# Neutron_v1.net
KiCad netlist of a schematic drawn in EAGLE
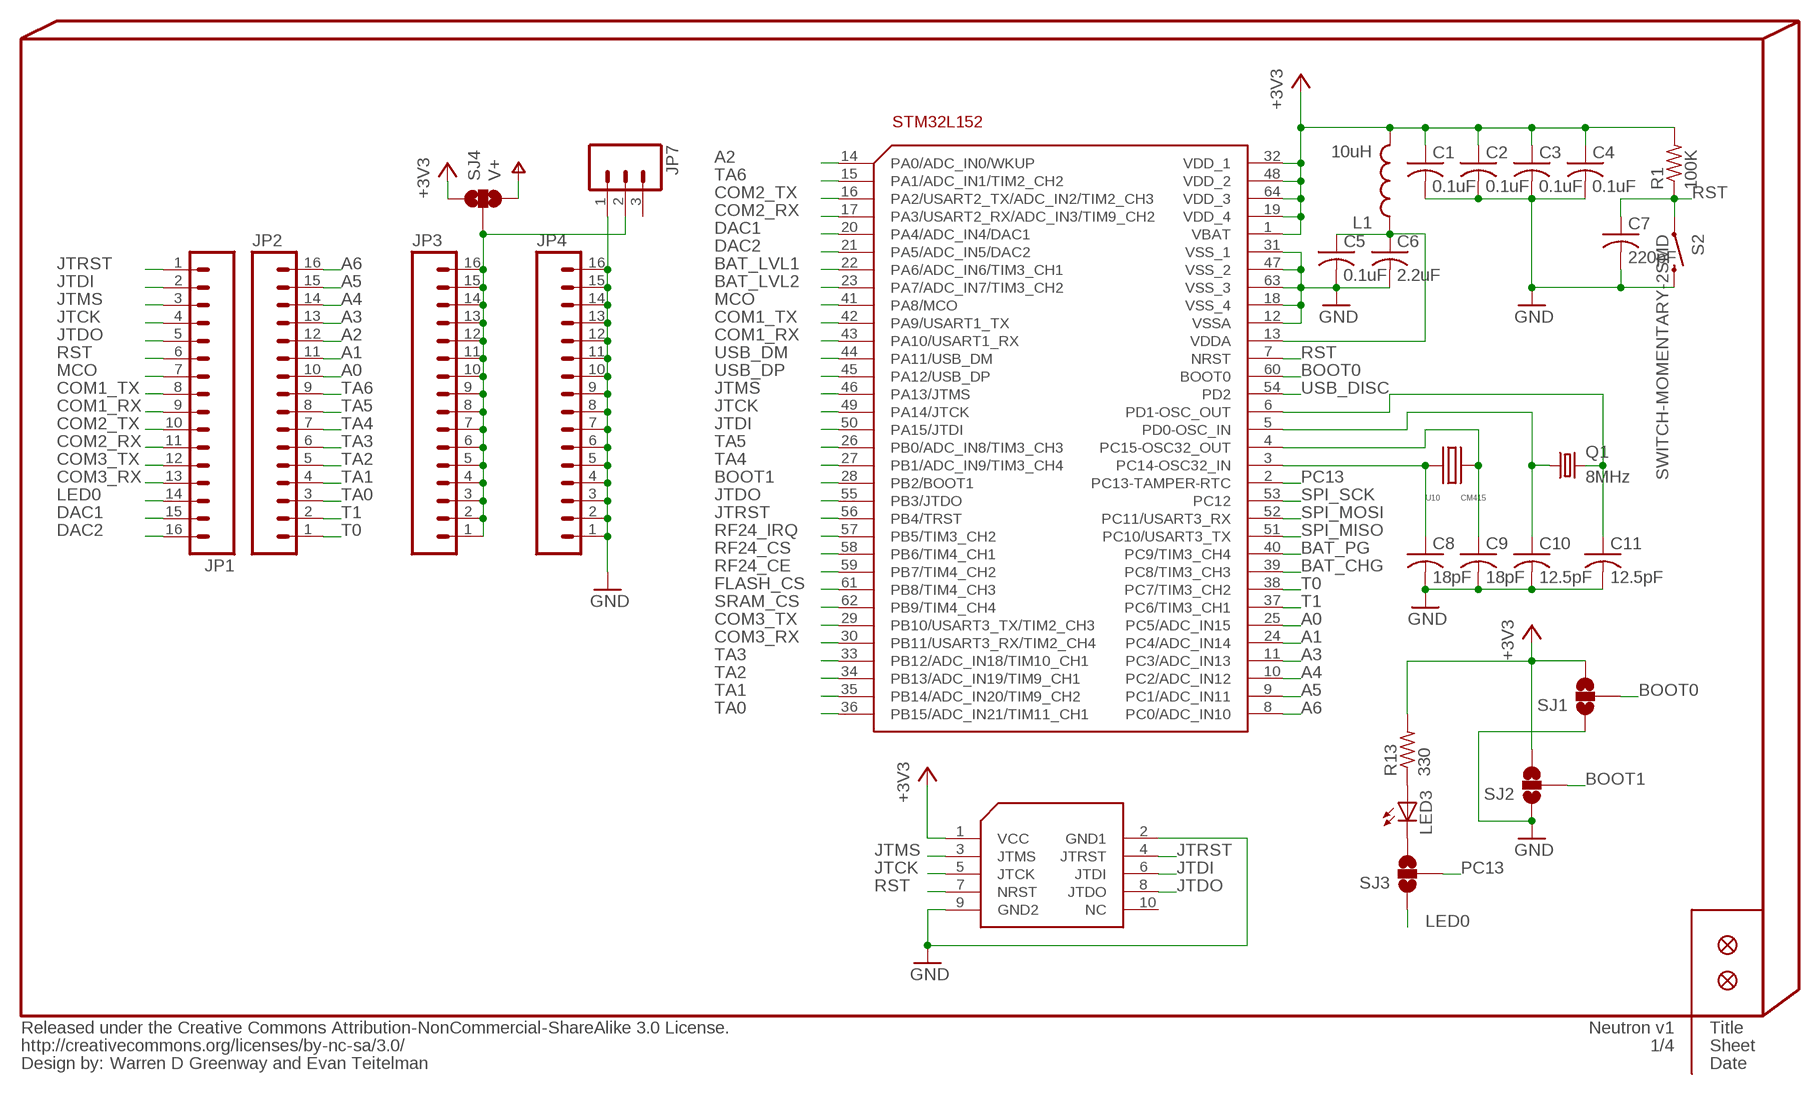
[diagram p0: schematic, sheet 1]
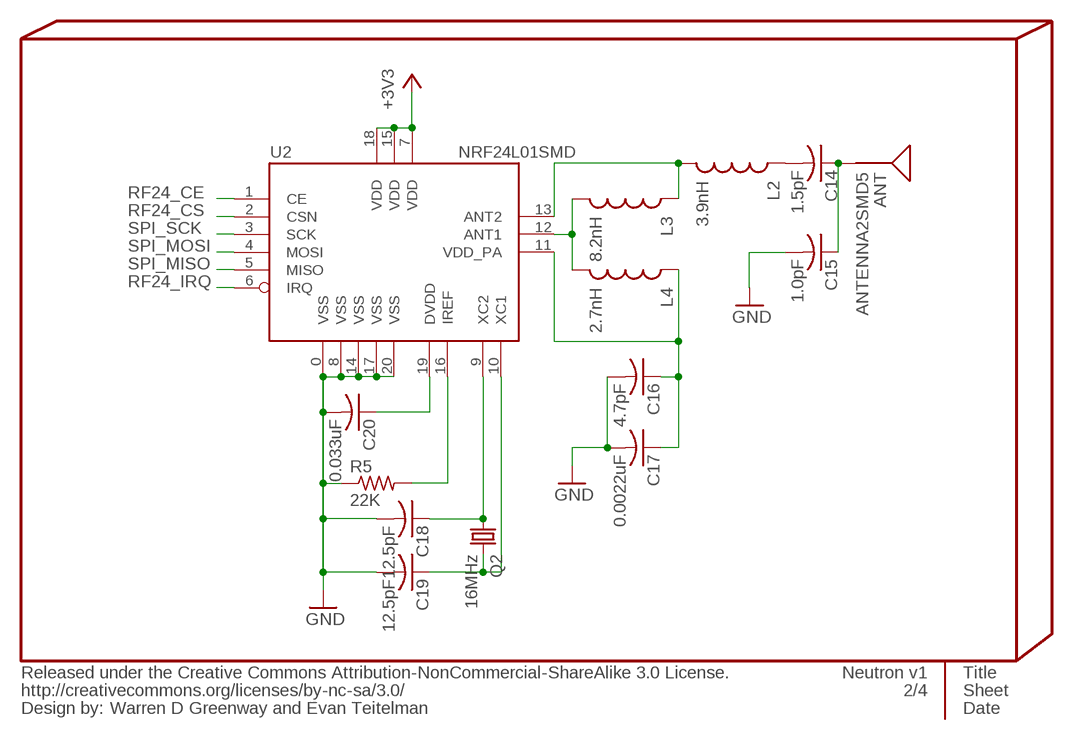
[diagram p1: schematic, sheet 2]
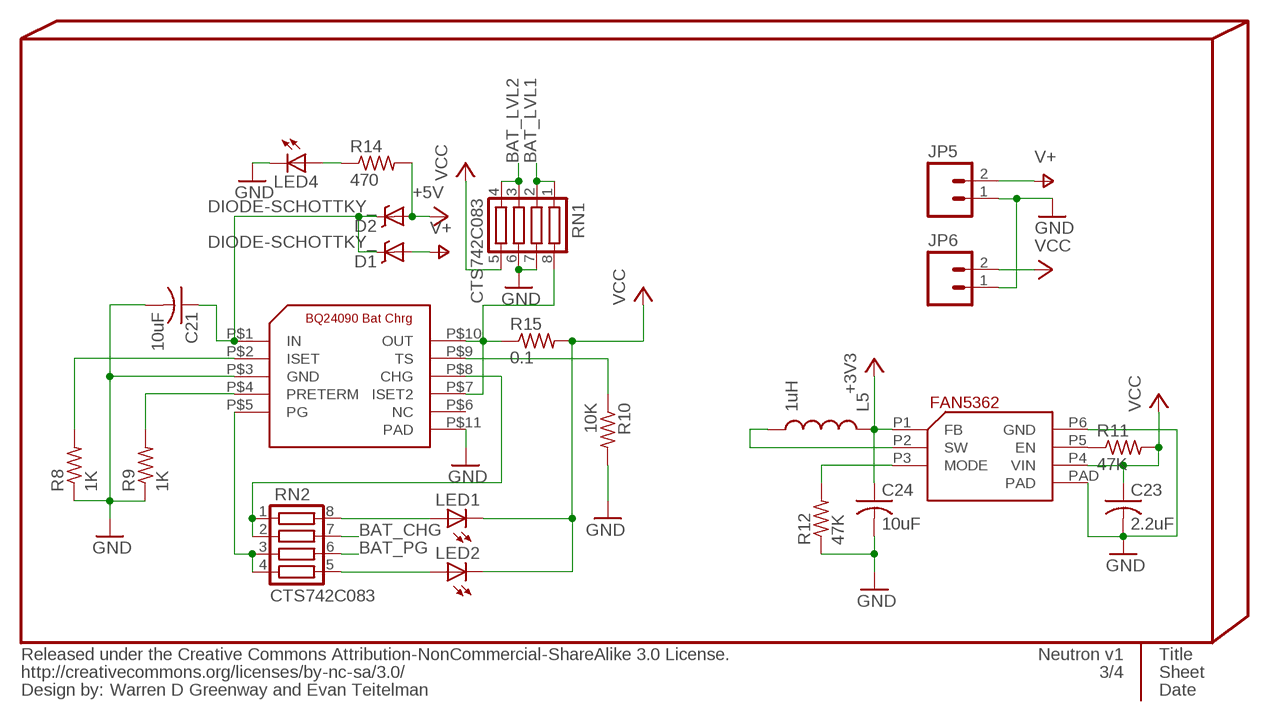
[diagram p2: schematic, sheet 3]
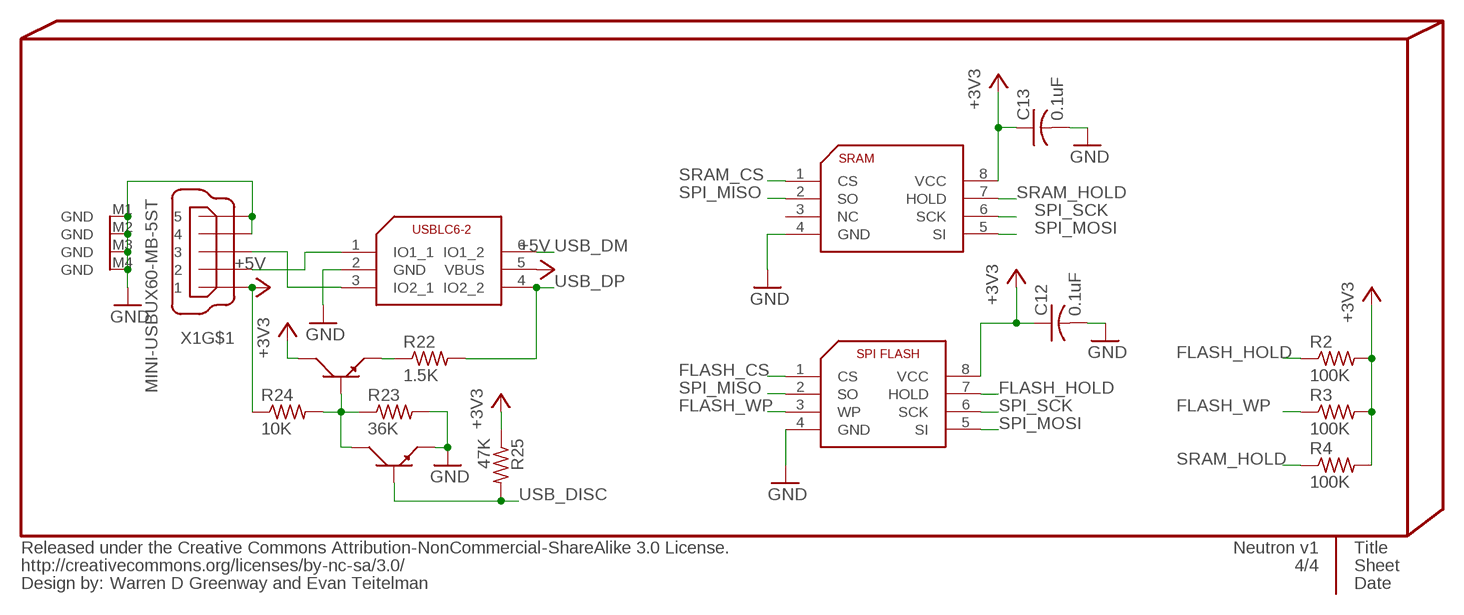
[diagram p3: schematic, sheet 4]

(export (version "E")
  (design (tool "Eeschema 10.0.6"))
  (components
    (comp (ref "ANT")
      (value "ANTENNA2SMD5")
      (footprint "eagle-import:ANTENNA-CHIP5")
      (libsource (lib "eagle-import") (part "ANTENNA2SMD5"))
    )
    (comp (ref "C14")
      (value "1.5pF")
      (footprint "eagle-import:C0402")
      (libsource (lib "eagle-import") (part "C-USC0402"))
    )
    (comp (ref "C15")
      (value "1.0pF")
      (footprint "eagle-import:C0402")
      (libsource (lib "eagle-import") (part "C-USC0402"))
    )
    (comp (ref "C16")
      (value "4.7pF")
      (footprint "eagle-import:C0402")
      (libsource (lib "eagle-import") (part "C-USC0402"))
    )
    (comp (ref "C17")
      (value "0.0022uF")
      (footprint "eagle-import:C0402")
      (libsource (lib "eagle-import") (part "C-USC0402"))
    )
    (comp (ref "C18")
      (value "12.5pF")
      (footprint "eagle-import:C0402")
      (libsource (lib "eagle-import") (part "C-USC0402"))
    )
    (comp (ref "C19")
      (value "12.5pF")
      (footprint "eagle-import:C0402")
      (libsource (lib "eagle-import") (part "C-USC0402"))
    )
    (comp (ref "C20")
      (value "0.033uF")
      (footprint "eagle-import:C0402")
      (libsource (lib "eagle-import") (part "C-USC0402"))
    )
    (comp (ref "L2")
      (value "3.9nH")
      (footprint "eagle-import:C0402")
      (libsource (lib "eagle-import") (part "INDUCTOR0402"))
    )
    (comp (ref "L3")
      (value "8.2nH")
      (footprint "eagle-import:C0402")
      (libsource (lib "eagle-import") (part "INDUCTOR0402"))
    )
    (comp (ref "L4")
      (value "2.7nH")
      (footprint "eagle-import:C0402")
      (libsource (lib "eagle-import") (part "INDUCTOR0402"))
    )
    (comp (ref "Q2")
      (value "16MHz")
      (footprint "eagle-import:CRYSTAL-SMD-5X3")
      (libsource (lib "eagle-import") (part "CRYSTAL5X3"))
    )
    (comp (ref "R5")
      (value "22K")
      (footprint "eagle-import:R0402")
      (libsource (lib "eagle-import") (part "R-US_R0402"))
    )
    (comp (ref "U2")
      (value "NRF24L01SMD")
      (footprint "eagle-import:QFN20")
      (libsource (lib "eagle-import") (part "NRF24L01SMD"))
    )
    (comp (ref "C12")
      (value "0.1uF")
      (footprint "eagle-import:C0402")
      (libsource (lib "eagle-import") (part "C-USC0402"))
    )
    (comp (ref "C13")
      (value "0.1uF")
      (footprint "eagle-import:C0402")
      (libsource (lib "eagle-import") (part "C-USC0402"))
    )
    (comp (ref "R2")
      (value "100K")
      (footprint "eagle-import:R0402")
      (libsource (lib "eagle-import") (part "R-US_R0402"))
    )
    (comp (ref "R3")
      (value "100K")
      (footprint "eagle-import:R0402")
      (libsource (lib "eagle-import") (part "R-US_R0402"))
    )
    (comp (ref "R4")
      (value "100K")
      (footprint "eagle-import:R0402")
      (libsource (lib "eagle-import") (part "R-US_R0402"))
    )
    (comp (ref "R22")
      (value "1.5K")
      (footprint "eagle-import:R0402")
      (libsource (lib "eagle-import") (part "R-US_R0402"))
    )
    (comp (ref "R23")
      (value "36K")
      (footprint "eagle-import:R0402")
      (libsource (lib "eagle-import") (part "R-US_R0402"))
    )
    (comp (ref "R24")
      (value "10K")
      (footprint "eagle-import:R0402")
      (libsource (lib "eagle-import") (part "R-US_R0402"))
    )
    (comp (ref "R25")
      (value "47K")
      (footprint "eagle-import:R0402")
      (libsource (lib "eagle-import") (part "R-US_R0402"))
    )
    (comp (ref "U4")
      (value "SST25VF080B")
      (footprint "eagle-import:DUBLIB_SOIC8")
      (libsource (lib "eagle-import") (part "SST25VF080B"))
    )
    (comp (ref "U5")
      (value "N25S0830HA")
      (footprint "eagle-import:TSSOP8")
      (libsource (lib "eagle-import") (part "N25S0830HA"))
    )
    (comp (ref "U6")
      (value "USBLC6-2")
      (footprint "eagle-import:SOT23-6L")
      (libsource (lib "eagle-import") (part "USBLC6-2"))
    )
    (comp (ref "U7")
      (value "BIPOLAR-PMBT6428")
      (footprint "eagle-import:DUBLIB_SOT23")
      (libsource (lib "eagle-import") (part "BIPOLAR-PMBT6428"))
    )
    (comp (ref "U8")
      (value "BIPOLAR-PMBT6428")
      (footprint "eagle-import:DUBLIB_SOT23")
      (libsource (lib "eagle-import") (part "BIPOLAR-PMBT6428"))
    )
    (comp (ref "X1")
      (value "MINI-USBUX60-MB-5ST")
      (footprint "eagle-import:DUBLIB_UX60-MB-5ST")
      (libsource (lib "eagle-import") (part "MINI-USBUX60-MB-5ST"))
    )
    (comp (ref "C1")
      (value "0.1uF")
      (footprint "eagle-import:C0402")
      (libsource (lib "eagle-import") (part "C-USC0402"))
    )
    (comp (ref "C2")
      (value "0.1uF")
      (footprint "eagle-import:C0402")
      (libsource (lib "eagle-import") (part "C-USC0402"))
    )
    (comp (ref "C3")
      (value "0.1uF")
      (footprint "eagle-import:C0402")
      (libsource (lib "eagle-import") (part "C-USC0402"))
    )
    (comp (ref "C4")
      (value "0.1uF")
      (footprint "eagle-import:C0402")
      (libsource (lib "eagle-import") (part "C-USC0402"))
    )
    (comp (ref "C5")
      (value "0.1uF")
      (footprint "eagle-import:C0402")
      (libsource (lib "eagle-import") (part "C-USC0402"))
    )
    (comp (ref "C6")
      (value "2.2uF")
      (footprint "eagle-import:C0402")
      (libsource (lib "eagle-import") (part "C-USC0402"))
    )
    (comp (ref "C7")
      (value "220pF")
      (footprint "eagle-import:C0402")
      (libsource (lib "eagle-import") (part "C-USC0402"))
    )
    (comp (ref "C8")
      (value "18pF")
      (footprint "eagle-import:C0402")
      (libsource (lib "eagle-import") (part "C-USC0402"))
    )
    (comp (ref "C9")
      (value "18pF")
      (footprint "eagle-import:C0402")
      (libsource (lib "eagle-import") (part "C-USC0402"))
    )
    (comp (ref "C10")
      (value "12.5pF")
      (footprint "eagle-import:C0402")
      (libsource (lib "eagle-import") (part "C-USC0402"))
    )
    (comp (ref "C11")
      (value "12.5pF")
      (footprint "eagle-import:C0402")
      (libsource (lib "eagle-import") (part "C-USC0402"))
    )
    (comp (ref "INFO4")
      (value "Warren D Greenway and Evan Teitelman")
      (footprint "eagle-import:%CC-NC-SA")
      (libsource (lib "eagle-import") (part "%CC-NC-SA"))
    )
    (comp (ref "JP1")
      (value "M16ALTSILKLAYER")
      (footprint "eagle-import:1X16SS")
      (libsource (lib "eagle-import") (part "M16ALTSILKLAYER"))
    )
    (comp (ref "JP2")
      (value "M16ALTSILKLAYER")
      (footprint "eagle-import:1X16SS")
      (libsource (lib "eagle-import") (part "M16ALTSILKLAYER"))
    )
    (comp (ref "JP3")
      (value "M16ALTSILKLAYER")
      (footprint "eagle-import:1X16SS")
      (libsource (lib "eagle-import") (part "M16ALTSILKLAYER"))
    )
    (comp (ref "JP4")
      (value "M16ALTSILKLAYER")
      (footprint "eagle-import:1X16SS")
      (libsource (lib "eagle-import") (part "M16ALTSILKLAYER"))
    )
    (comp (ref "JP7")
      (value "M03ALTSILKLAYER")
      (footprint "eagle-import:1X03SS")
      (libsource (lib "eagle-import") (part "M03ALTSILKLAYER"))
    )
    (comp (ref "JP8")
      (value "FIDUCIAL1.5X3")
      (footprint "eagle-import:FIDUCIAL-1.5X3")
      (libsource (lib "eagle-import") (part "FIDUCIAL1.5X3"))
    )
    (comp (ref "JP9")
      (value "FIDUCIAL1.5X3")
      (footprint "eagle-import:FIDUCIAL-1.5X3")
      (libsource (lib "eagle-import") (part "FIDUCIAL1.5X3"))
    )
    (comp (ref "L1")
      (value "10uH")
      (footprint "eagle-import:0603")
      (libsource (lib "eagle-import") (part "INDUCTOR0603"))
    )
    (comp (ref "LED3")
      (value "LED0603")
      (footprint "eagle-import:LED-0603")
      (libsource (lib "eagle-import") (part "LED0603"))
    )
    (comp (ref "Q1")
      (value "8MHz")
      (footprint "eagle-import:CRYSTAL-SMD-5X3")
      (libsource (lib "eagle-import") (part "CRYSTAL5X3"))
    )
    (comp (ref "R1")
      (value "100K")
      (footprint "eagle-import:R0402")
      (libsource (lib "eagle-import") (part "R-US_R0402"))
    )
    (comp (ref "R13")
      (value "330")
      (footprint "eagle-import:R0402")
      (libsource (lib "eagle-import") (part "R-US_R0402"))
    )
    (comp (ref "S2")
      (value "SWITCH-MOMENTARY-2SMD")
      (footprint "eagle-import:SPARKFUN_TACTILE_SWITCH_SMD")
      (libsource (lib "eagle-import") (part "SWITCH-MOMENTARY-2SMD"))
    )
    (comp (ref "SJ1")
      (value "SOLDERJUMPER_2WAYS")
      (footprint "eagle-import:SJ_3")
      (libsource (lib "eagle-import") (part "SOLDERJUMPER_2WAYS"))
    )
    (comp (ref "SJ2")
      (value "SOLDERJUMPER_2WAYS")
      (footprint "eagle-import:SJ_3")
      (libsource (lib "eagle-import") (part "SOLDERJUMPER_2WAYS"))
    )
    (comp (ref "SJ3")
      (value "SOLDERJUMPER_2WAYS")
      (footprint "eagle-import:SJ_3")
      (libsource (lib "eagle-import") (part "SOLDERJUMPER_2WAYS"))
    )
    (comp (ref "SJ4")
      (value "SOLDERJUMPER_2WAYT")
      (footprint "eagle-import:SJ_2")
      (libsource (lib "eagle-import") (part "SOLDERJUMPER_2WAYT"))
    )
    (comp (ref "U$2")
      (value "STM32-JTAG-10P")
      (footprint "eagle-import:STM32-JTAG-10P")
      (libsource (lib "eagle-import") (part "STM32-JTAG-10P"))
    )
    (comp (ref "U1")
      (value "STM32L152")
      (footprint "eagle-import:S-PQFP64-G64")
      (libsource (lib "eagle-import") (part "STM32L152"))
    )
    (comp (ref "U10")
      (value "CM415")
      (footprint "eagle-import:CM415")
      (libsource (lib "eagle-import") (part "CM415"))
    )
    (comp (ref "C21")
      (value "10uF")
      (footprint "eagle-import:C0805")
      (libsource (lib "eagle-import") (part "C-USC0805"))
    )
    (comp (ref "C23")
      (value "2.2uF")
      (footprint "eagle-import:C0402")
      (libsource (lib "eagle-import") (part "C-USC0402"))
    )
    (comp (ref "C24")
      (value "10uF")
      (footprint "eagle-import:C0805")
      (libsource (lib "eagle-import") (part "C-USC0805"))
    )
    (comp (ref "D1")
      (value "DIODE-SCHOTTKY_")
      (footprint "eagle-import:SMA-DIODE")
      (libsource (lib "eagle-import") (part "DIODE-SCHOTTKY_"))
    )
    (comp (ref "D2")
      (value "DIODE-SCHOTTKY_")
      (footprint "eagle-import:SMA-DIODE")
      (libsource (lib "eagle-import") (part "DIODE-SCHOTTKY_"))
    )
    (comp (ref "JP5")
      (value "M02JST-PTH-2")
      (footprint "eagle-import:JST-2-PTH")
      (libsource (lib "eagle-import") (part "M02JST-PTH-2"))
    )
    (comp (ref "JP6")
      (value "M02JST-PTH-2")
      (footprint "eagle-import:JST-2-PTH")
      (libsource (lib "eagle-import") (part "M02JST-PTH-2"))
    )
    (comp (ref "L5")
      (value "1uH")
      (footprint "eagle-import:0805")
      (libsource (lib "eagle-import") (part "INDUCTOR0805"))
    )
    (comp (ref "LED1")
      (value "LED0603")
      (footprint "eagle-import:LED-0603")
      (libsource (lib "eagle-import") (part "LED0603"))
    )
    (comp (ref "LED2")
      (value "LED0603")
      (footprint "eagle-import:LED-0603")
      (libsource (lib "eagle-import") (part "LED0603"))
    )
    (comp (ref "LED4")
      (value "LED0603")
      (footprint "eagle-import:LED-0603")
      (libsource (lib "eagle-import") (part "LED0603"))
    )
    (comp (ref "R8")
      (value "1K")
      (footprint "eagle-import:R0402")
      (libsource (lib "eagle-import") (part "R-US_R0402"))
    )
    (comp (ref "R9")
      (value "1K")
      (footprint "eagle-import:R0402")
      (libsource (lib "eagle-import") (part "R-US_R0402"))
    )
    (comp (ref "R10")
      (value "10K")
      (footprint "eagle-import:R0402")
      (libsource (lib "eagle-import") (part "R-US_R0402"))
    )
    (comp (ref "R11")
      (value "47K")
      (footprint "eagle-import:R0402")
      (libsource (lib "eagle-import") (part "R-US_R0402"))
    )
    (comp (ref "R12")
      (value "47K")
      (footprint "eagle-import:R0402")
      (libsource (lib "eagle-import") (part "R-US_R0402"))
    )
    (comp (ref "R14")
      (value "470")
      (footprint "eagle-import:R0402")
      (libsource (lib "eagle-import") (part "R-US_R0402"))
    )
    (comp (ref "R15")
      (value "0.1")
      (footprint "eagle-import:R0805")
      (libsource (lib "eagle-import") (part "R-US_R0805"))
    )
    (comp (ref "RN1")
      (value "CTS742C083")
      (footprint "eagle-import:CTS742C083")
      (libsource (lib "eagle-import") (part "CTS742C083"))
    )
    (comp (ref "RN2")
      (value "CTS742C083")
      (footprint "eagle-import:CTS742C083")
      (libsource (lib "eagle-import") (part "CTS742C083"))
    )
    (comp (ref "U3")
      (value "BQ24090")
      (footprint "eagle-import:R-PDSO-G10")
      (libsource (lib "eagle-import") (part "BQ24090"))
    )
    (comp (ref "U9")
      (value "FAIRCHILD-REG-FAN5362")
      (footprint "eagle-import:MO229")
      (libsource (lib "eagle-import") (part "FAIRCHILD-REG-FAN5362"))
    )
  )
  (nets
    (net (code "1") (name "+3V3") (class "Default")
      (node (ref "C1") (pin "1") (pinfunction "1_1") (pintype "passive"))
      (node (ref "C12") (pin "1") (pinfunction "1_1") (pintype "passive"))
      (node (ref "C13") (pin "1") (pinfunction "1_1") (pintype "passive"))
      (node (ref "C2") (pin "1") (pinfunction "1_1") (pintype "passive"))
      (node (ref "C24") (pin "1") (pinfunction "1_1") (pintype "passive"))
      (node (ref "C3") (pin "1") (pinfunction "1_1") (pintype "passive"))
      (node (ref "C4") (pin "1") (pinfunction "1_1") (pintype "passive"))
      (node (ref "L1") (pin "2") (pinfunction "2_2") (pintype "passive"))
      (node (ref "L5") (pin "1") (pinfunction "1_1") (pintype "passive"))
      (node (ref "R1") (pin "2") (pinfunction "2_2") (pintype "passive"))
      (node (ref "R13") (pin "2") (pinfunction "2_2") (pintype "passive"))
      (node (ref "R2") (pin "2") (pinfunction "2_2") (pintype "passive"))
      (node (ref "R25") (pin "1") (pinfunction "1_1") (pintype "passive"))
      (node (ref "R3") (pin "2") (pinfunction "2_2") (pintype "passive"))
      (node (ref "R4") (pin "2") (pinfunction "2_2") (pintype "passive"))
      (node (ref "SJ1") (pin "3") (pinfunction "3_3") (pintype "passive"))
      (node (ref "SJ2") (pin "3") (pinfunction "3_3") (pintype "passive"))
      (node (ref "SJ4") (pin "1") (pinfunction "1_1") (pintype "passive"))
      (node (ref "U$2") (pin "1") (pinfunction "VCC_1") (pintype "bidirectional"))
      (node (ref "U1") (pin "1") (pinfunction "VBAT_1") (pintype "bidirectional"))
      (node (ref "U1") (pin "19") (pinfunction "VDD_4_19") (pintype "bidirectional"))
      (node (ref "U1") (pin "32") (pinfunction "VDD_1_32") (pintype "bidirectional"))
      (node (ref "U1") (pin "48") (pinfunction "VDD_2_48") (pintype "bidirectional"))
      (node (ref "U1") (pin "64") (pinfunction "VDD_3_64") (pintype "bidirectional"))
      (node (ref "U2") (pin "15") (pinfunction "VDD_15") (pintype "power_in"))
      (node (ref "U2") (pin "18") (pinfunction "VDD_18") (pintype "power_in"))
      (node (ref "U2") (pin "7") (pinfunction "VDD_7") (pintype "power_in"))
      (node (ref "U4") (pin "8") (pinfunction "VCC_8") (pintype "bidirectional"))
      (node (ref "U5") (pin "8") (pinfunction "VCC_8") (pintype "bidirectional"))
      (node (ref "U7") (pin "3") (pinfunction "3_3") (pintype "bidirectional"))
      (node (ref "U9") (pin "P1") (pinfunction "FB_P1") (pintype "bidirectional"))
    )
    (net (code "2") (name "+5V") (class "Default")
      (node (ref "D2") (pin "A") (pinfunction "A_A") (pintype "passive"))
      (node (ref "R14") (pin "2") (pinfunction "2_2") (pintype "passive"))
      (node (ref "R24") (pin "1") (pinfunction "1_1") (pintype "passive"))
      (node (ref "U6") (pin "5") (pinfunction "VBUS_5") (pintype "bidirectional"))
      (node (ref "X1") (pin "1") (pinfunction "1_1") (pintype "input"))
    )
    (net (code "3") (name "A0") (class "Default")
      (node (ref "JP2") (pin "10") (pinfunction "10_10") (pintype "passive"))
      (node (ref "U1") (pin "25") (pinfunction "PC5/ADC_IN15_25") (pintype "bidirectional"))
    )
    (net (code "4") (name "A1") (class "Default")
      (node (ref "JP2") (pin "11") (pinfunction "11_11") (pintype "passive"))
      (node (ref "U1") (pin "24") (pinfunction "PC4/ADC_IN14_24") (pintype "bidirectional"))
    )
    (net (code "5") (name "A2") (class "Default")
      (node (ref "JP2") (pin "12") (pinfunction "12_12") (pintype "passive"))
      (node (ref "U1") (pin "14") (pinfunction "PA0/ADC_IN0/WKUP_14") (pintype "bidirectional"))
    )
    (net (code "6") (name "A3") (class "Default")
      (node (ref "JP2") (pin "13") (pinfunction "13_13") (pintype "passive"))
      (node (ref "U1") (pin "11") (pinfunction "PC3/ADC_IN13_11") (pintype "bidirectional"))
    )
    (net (code "7") (name "A4") (class "Default")
      (node (ref "JP2") (pin "14") (pinfunction "14_14") (pintype "passive"))
      (node (ref "U1") (pin "10") (pinfunction "PC2/ADC_IN12_10") (pintype "bidirectional"))
    )
    (net (code "8") (name "A5") (class "Default")
      (node (ref "JP2") (pin "15") (pinfunction "15_15") (pintype "passive"))
      (node (ref "U1") (pin "9") (pinfunction "PC1/ADC_IN11_9") (pintype "bidirectional"))
    )
    (net (code "9") (name "A6") (class "Default")
      (node (ref "JP2") (pin "16") (pinfunction "16_16") (pintype "passive"))
      (node (ref "U1") (pin "8") (pinfunction "PC0/ADC_IN10_8") (pintype "bidirectional"))
    )
    (net (code "10") (name "BAT_CHG") (class "Default")
      (node (ref "RN2") (pin "7") (pinfunction "7_7") (pintype "passive"))
      (node (ref "U1") (pin "39") (pinfunction "PC8/TIM3_CH3_39") (pintype "bidirectional"))
    )
    (net (code "11") (name "BAT_LVL1") (class "Default")
      (node (ref "RN1") (pin "1") (pinfunction "1_1") (pintype "passive"))
      (node (ref "RN1") (pin "2") (pinfunction "2_2") (pintype "passive"))
      (node (ref "U1") (pin "22") (pinfunction "PA6/ADC_IN6/TIM3_CH1_22") (pintype "bidirectional"))
    )
    (net (code "12") (name "BAT_LVL2") (class "Default")
      (node (ref "RN1") (pin "3") (pinfunction "3_3") (pintype "passive"))
      (node (ref "RN1") (pin "4") (pinfunction "4_4") (pintype "passive"))
      (node (ref "U1") (pin "23") (pinfunction "PA7/ADC_IN7/TIM3_CH2_23") (pintype "bidirectional"))
    )
    (net (code "13") (name "BAT_PG") (class "Default")
      (node (ref "RN2") (pin "6") (pinfunction "6_6") (pintype "passive"))
      (node (ref "U1") (pin "40") (pinfunction "PC9/TIM3_CH4_40") (pintype "bidirectional"))
    )
    (net (code "14") (name "BOOT0") (class "Default")
      (node (ref "SJ1") (pin "2") (pinfunction "2_2") (pintype "passive"))
      (node (ref "U1") (pin "60") (pinfunction "BOOT0_60") (pintype "bidirectional"))
    )
    (net (code "15") (name "BOOT1") (class "Default")
      (node (ref "SJ2") (pin "2") (pinfunction "2_2") (pintype "passive"))
      (node (ref "U1") (pin "28") (pinfunction "PB2/BOOT1_28") (pintype "bidirectional"))
    )
    (net (code "16") (name "COM1_RX") (class "Default")
      (node (ref "JP1") (pin "9") (pinfunction "9_9") (pintype "passive"))
      (node (ref "U1") (pin "43") (pinfunction "PA10/USART1_RX_43") (pintype "bidirectional"))
    )
    (net (code "17") (name "COM1_TX") (class "Default")
      (node (ref "JP1") (pin "8") (pinfunction "8_8") (pintype "passive"))
      (node (ref "U1") (pin "42") (pinfunction "PA9/USART1_TX_42") (pintype "bidirectional"))
    )
    (net (code "18") (name "COM2_RX") (class "Default")
      (node (ref "JP1") (pin "11") (pinfunction "11_11") (pintype "passive"))
      (node (ref "U1") (pin "17") (pinfunction "PA3/USART2_RX/ADC_IN3/TIM9_CH2_17") (pintype "bidirectional"))
    )
    (net (code "19") (name "COM2_TX") (class "Default")
      (node (ref "JP1") (pin "10") (pinfunction "10_10") (pintype "passive"))
      (node (ref "U1") (pin "16") (pinfunction "PA2/USART2_TX/ADC_IN2/TIM2_CH3_16") (pintype "bidirectional"))
    )
    (net (code "20") (name "COM3_RX") (class "Default")
      (node (ref "JP1") (pin "13") (pinfunction "13_13") (pintype "passive"))
      (node (ref "U1") (pin "30") (pinfunction "PB11/USART3_RX/TIM2_CH4_30") (pintype "bidirectional"))
    )
    (net (code "21") (name "COM3_TX") (class "Default")
      (node (ref "JP1") (pin "12") (pinfunction "12_12") (pintype "passive"))
      (node (ref "U1") (pin "29") (pinfunction "PB10/USART3_TX/TIM2_CH3_29") (pintype "bidirectional"))
    )
    (net (code "22") (name "DAC1") (class "Default")
      (node (ref "JP1") (pin "15") (pinfunction "15_15") (pintype "passive"))
      (node (ref "U1") (pin "20") (pinfunction "PA4/ADC_IN4/DAC1_20") (pintype "bidirectional"))
    )
    (net (code "23") (name "DAC2") (class "Default")
      (node (ref "JP1") (pin "16") (pinfunction "16_16") (pintype "passive"))
      (node (ref "U1") (pin "21") (pinfunction "PA5/ADC_IN5/DAC2_21") (pintype "bidirectional"))
    )
    (net (code "24") (name "FLASH_CS") (class "Default")
      (node (ref "U1") (pin "61") (pinfunction "PB8/TIM4_CH3_61") (pintype "bidirectional"))
      (node (ref "U4") (pin "1") (pinfunction "CS_1") (pintype "bidirectional"))
    )
    (net (code "25") (name "FLASH_HOLD") (class "Default")
      (node (ref "R2") (pin "1") (pinfunction "1_1") (pintype "passive"))
      (node (ref "U4") (pin "7") (pinfunction "HOLD_7") (pintype "bidirectional"))
    )
    (net (code "26") (name "FLASH_WP") (class "Default")
      (node (ref "R3") (pin "1") (pinfunction "1_1") (pintype "passive"))
      (node (ref "U4") (pin "3") (pinfunction "WP_3") (pintype "bidirectional"))
    )
    (net (code "27") (name "GND") (class "Default")
      (node (ref "C1") (pin "2") (pinfunction "2_2") (pintype "passive"))
      (node (ref "C10") (pin "2") (pinfunction "2_2") (pintype "passive"))
      (node (ref "C11") (pin "2") (pinfunction "2_2") (pintype "passive"))
      (node (ref "C12") (pin "2") (pinfunction "2_2") (pintype "passive"))
      (node (ref "C13") (pin "2") (pinfunction "2_2") (pintype "passive"))
      (node (ref "C15") (pin "2") (pinfunction "2_2") (pintype "passive"))
      (node (ref "C16") (pin "2") (pinfunction "2_2") (pintype "passive"))
      (node (ref "C17") (pin "2") (pinfunction "2_2") (pintype "passive"))
      (node (ref "C18") (pin "2") (pinfunction "2_2") (pintype "passive"))
      (node (ref "C19") (pin "2") (pinfunction "2_2") (pintype "passive"))
      (node (ref "C2") (pin "2") (pinfunction "2_2") (pintype "passive"))
      (node (ref "C20") (pin "2") (pinfunction "2_2") (pintype "passive"))
      (node (ref "C21") (pin "2") (pinfunction "2_2") (pintype "passive"))
      (node (ref "C23") (pin "2") (pinfunction "2_2") (pintype "passive"))
      (node (ref "C24") (pin "2") (pinfunction "2_2") (pintype "passive"))
      (node (ref "C3") (pin "2") (pinfunction "2_2") (pintype "passive"))
      (node (ref "C4") (pin "2") (pinfunction "2_2") (pintype "passive"))
      (node (ref "C5") (pin "2") (pinfunction "2_2") (pintype "passive"))
      (node (ref "C6") (pin "2") (pinfunction "2_2") (pintype "passive"))
      (node (ref "C7") (pin "2") (pinfunction "2_2") (pintype "passive"))
      (node (ref "C8") (pin "2") (pinfunction "2_2") (pintype "passive"))
      (node (ref "C9") (pin "2") (pinfunction "2_2") (pintype "passive"))
      (node (ref "JP4") (pin "1") (pinfunction "1_1") (pintype "passive"))
      (node (ref "JP4") (pin "10") (pinfunction "10_10") (pintype "passive"))
      (node (ref "JP4") (pin "11") (pinfunction "11_11") (pintype "passive"))
      (node (ref "JP4") (pin "12") (pinfunction "12_12") (pintype "passive"))
      (node (ref "JP4") (pin "13") (pinfunction "13_13") (pintype "passive"))
      (node (ref "JP4") (pin "14") (pinfunction "14_14") (pintype "passive"))
      (node (ref "JP4") (pin "15") (pinfunction "15_15") (pintype "passive"))
      (node (ref "JP4") (pin "16") (pinfunction "16_16") (pintype "passive"))
      (node (ref "JP4") (pin "2") (pinfunction "2_2") (pintype "passive"))
      (node (ref "JP4") (pin "3") (pinfunction "3_3") (pintype "passive"))
      (node (ref "JP4") (pin "4") (pinfunction "4_4") (pintype "passive"))
      (node (ref "JP4") (pin "5") (pinfunction "5_5") (pintype "passive"))
      (node (ref "JP4") (pin "6") (pinfunction "6_6") (pintype "passive"))
      (node (ref "JP4") (pin "7") (pinfunction "7_7") (pintype "passive"))
      (node (ref "JP4") (pin "8") (pinfunction "8_8") (pintype "passive"))
      (node (ref "JP4") (pin "9") (pinfunction "9_9") (pintype "passive"))
      (node (ref "JP5") (pin "1") (pinfunction "1_1") (pintype "passive"))
      (node (ref "JP6") (pin "1") (pinfunction "1_1") (pintype "passive"))
      (node (ref "JP7") (pin "1") (pinfunction "1_1") (pintype "passive"))
      (node (ref "LED4") (pin "C") (pinfunction "C_C") (pintype "passive"))
      (node (ref "R10") (pin "2") (pinfunction "2_2") (pintype "passive"))
      (node (ref "R12") (pin "1") (pinfunction "1_1") (pintype "passive"))
      (node (ref "R23") (pin "2") (pinfunction "2_2") (pintype "passive"))
      (node (ref "R5") (pin "1") (pinfunction "1_1") (pintype "passive"))
      (node (ref "R8") (pin "1") (pinfunction "1_1") (pintype "passive"))
      (node (ref "R9") (pin "1") (pinfunction "1_1") (pintype "passive"))
      (node (ref "RN1") (pin "6") (pinfunction "6_6") (pintype "passive"))
      (node (ref "RN1") (pin "7") (pinfunction "7_7") (pintype "passive"))
      (node (ref "S2") (pin "3") (pinfunction "2_3") (pintype "passive"))
      (node (ref "SJ1") (pin "1") (pinfunction "1_1") (pintype "passive"))
      (node (ref "SJ2") (pin "1") (pinfunction "1_1") (pintype "passive"))
      (node (ref "U$2") (pin "2") (pinfunction "GND1_2") (pintype "bidirectional"))
      (node (ref "U$2") (pin "9") (pinfunction "GND2_9") (pintype "bidirectional"))
      (node (ref "U1") (pin "12") (pinfunction "VSSA_12") (pintype "bidirectional"))
      (node (ref "U1") (pin "18") (pinfunction "VSS_4_18") (pintype "bidirectional"))
      (node (ref "U1") (pin "31") (pinfunction "VSS_1_31") (pintype "bidirectional"))
      (node (ref "U1") (pin "47") (pinfunction "VSS_2_47") (pintype "bidirectional"))
      (node (ref "U1") (pin "63") (pinfunction "VSS_3_63") (pintype "bidirectional"))
      (node (ref "U2") (pin "0") (pinfunction "VSS_0") (pintype "power_in"))
      (node (ref "U2") (pin "14") (pinfunction "VSS_14") (pintype "power_in"))
      (node (ref "U2") (pin "17") (pinfunction "VSS_17") (pintype "power_in"))
      (node (ref "U2") (pin "20") (pinfunction "VSS_20") (pintype "power_in"))
      (node (ref "U2") (pin "8") (pinfunction "VSS_8") (pintype "power_in"))
      (node (ref "U3") (pin "P$11") (pinfunction "PAD_P$11") (pintype "bidirectional"))
      (node (ref "U3") (pin "P$3") (pinfunction "GND_P$3") (pintype "bidirectional"))
      (node (ref "U4") (pin "4") (pinfunction "GND_4") (pintype "bidirectional"))
      (node (ref "U5") (pin "4") (pinfunction "GND_4") (pintype "bidirectional"))
      (node (ref "U6") (pin "2") (pinfunction "GND_2") (pintype "bidirectional"))
      (node (ref "U8") (pin "2") (pinfunction "2_2") (pintype "bidirectional"))
      (node (ref "U9") (pin "P6") (pinfunction "GND_P6") (pintype "bidirectional"))
      (node (ref "U9") (pin "PAD") (pinfunction "PAD_PAD") (pintype "bidirectional"))
      (node (ref "X1") (pin "4") (pinfunction "4_4") (pintype "input"))
      (node (ref "X1") (pin "5") (pinfunction "5_5") (pintype "input"))
      (node (ref "X1") (pin "M1") (pinfunction "GND_M1") (pintype "power_in"))
      (node (ref "X1") (pin "M2") (pinfunction "GND_M2") (pintype "power_in"))
      (node (ref "X1") (pin "M3") (pinfunction "GND_M3") (pintype "power_in"))
      (node (ref "X1") (pin "M4") (pinfunction "GND_M4") (pintype "power_in"))
    )
    (net (code "28") (name "JTCK") (class "Default")
      (node (ref "JP1") (pin "4") (pinfunction "4_4") (pintype "passive"))
      (node (ref "U$2") (pin "5") (pinfunction "JTCK_5") (pintype "bidirectional"))
      (node (ref "U1") (pin "49") (pinfunction "PA14/JTCK_49") (pintype "bidirectional"))
    )
    (net (code "29") (name "JTDI") (class "Default")
      (node (ref "JP1") (pin "2") (pinfunction "2_2") (pintype "passive"))
      (node (ref "U$2") (pin "6") (pinfunction "JTDI_6") (pintype "bidirectional"))
      (node (ref "U1") (pin "50") (pinfunction "PA15/JTDI_50") (pintype "bidirectional"))
    )
    (net (code "30") (name "JTDO") (class "Default")
      (node (ref "JP1") (pin "5") (pinfunction "5_5") (pintype "passive"))
      (node (ref "U$2") (pin "8") (pinfunction "JTDO_8") (pintype "bidirectional"))
      (node (ref "U1") (pin "55") (pinfunction "PB3/JTDO_55") (pintype "bidirectional"))
    )
    (net (code "31") (name "JTMS") (class "Default")
      (node (ref "JP1") (pin "3") (pinfunction "3_3") (pintype "passive"))
      (node (ref "U$2") (pin "3") (pinfunction "JTMS_3") (pintype "bidirectional"))
      (node (ref "U1") (pin "46") (pinfunction "PA13/JTMS_46") (pintype "bidirectional"))
    )
    (net (code "32") (name "JTRST") (class "Default")
      (node (ref "JP1") (pin "1") (pinfunction "1_1") (pintype "passive"))
      (node (ref "U$2") (pin "4") (pinfunction "JTRST_4") (pintype "bidirectional"))
      (node (ref "U1") (pin "56") (pinfunction "PB4/TRST_56") (pintype "bidirectional"))
    )
    (net (code "33") (name "LED0") (class "Default")
      (node (ref "JP1") (pin "14") (pinfunction "14_14") (pintype "passive"))
      (node (ref "SJ3") (pin "1") (pinfunction "1_1") (pintype "passive"))
    )
    (net (code "34") (name "MCO") (class "Default")
      (node (ref "JP1") (pin "7") (pinfunction "7_7") (pintype "passive"))
      (node (ref "U1") (pin "41") (pinfunction "PA8/MCO_41") (pintype "bidirectional"))
    )
    (net (code "35") (name "Net-(ANT-SIGNAL)") (class "Default")
      (node (ref "ANT") (pin "FEED") (pinfunction "SIGNAL_FEED") (pintype "bidirectional"))
      (node (ref "C14") (pin "1") (pinfunction "1_1") (pintype "passive"))
      (node (ref "C15") (pin "1") (pinfunction "1_1") (pintype "passive"))
    )
    (net (code "36") (name "Net-(C14-Pad2)") (class "Default")
      (node (ref "C14") (pin "2") (pinfunction "2_2") (pintype "passive"))
      (node (ref "L2") (pin "1") (pinfunction "1_1") (pintype "passive"))
    )
    (net (code "37") (name "Net-(JP3-Pad1)") (class "Default")
      (node (ref "JP3") (pin "1") (pinfunction "1_1") (pintype "passive"))
      (node (ref "JP3") (pin "10") (pinfunction "10_10") (pintype "passive"))
      (node (ref "JP3") (pin "11") (pinfunction "11_11") (pintype "passive"))
      (node (ref "JP3") (pin "12") (pinfunction "12_12") (pintype "passive"))
      (node (ref "JP3") (pin "13") (pinfunction "13_13") (pintype "passive"))
      (node (ref "JP3") (pin "14") (pinfunction "14_14") (pintype "passive"))
      (node (ref "JP3") (pin "15") (pinfunction "15_15") (pintype "passive"))
      (node (ref "JP3") (pin "16") (pinfunction "16_16") (pintype "passive"))
      (node (ref "JP3") (pin "2") (pinfunction "2_2") (pintype "passive"))
      (node (ref "JP3") (pin "3") (pinfunction "3_3") (pintype "passive"))
      (node (ref "JP3") (pin "4") (pinfunction "4_4") (pintype "passive"))
      (node (ref "JP3") (pin "5") (pinfunction "5_5") (pintype "passive"))
      (node (ref "JP3") (pin "6") (pinfunction "6_6") (pintype "passive"))
      (node (ref "JP3") (pin "7") (pinfunction "7_7") (pintype "passive"))
      (node (ref "JP3") (pin "8") (pinfunction "8_8") (pintype "passive"))
      (node (ref "JP3") (pin "9") (pinfunction "9_9") (pintype "passive"))
      (node (ref "JP7") (pin "2") (pinfunction "2_2") (pintype "passive"))
      (node (ref "SJ4") (pin "2") (pinfunction "2_2") (pintype "passive"))
    )
    (net (code "38") (name "Net-(LED1-PadA)") (class "Default")
      (node (ref "LED1") (pin "A") (pinfunction "A_A") (pintype "passive"))
      (node (ref "RN2") (pin "8") (pinfunction "8_8") (pintype "passive"))
    )
    (net (code "39") (name "Net-(LED2-PadA)") (class "Default")
      (node (ref "LED2") (pin "A") (pinfunction "A_A") (pintype "passive"))
      (node (ref "RN2") (pin "5") (pinfunction "5_5") (pintype "passive"))
    )
    (net (code "40") (name "Net-(LED3-PadA)") (class "Default")
      (node (ref "LED3") (pin "A") (pinfunction "A_A") (pintype "passive"))
      (node (ref "R13") (pin "1") (pinfunction "1_1") (pintype "passive"))
    )
    (net (code "41") (name "Net-(LED3-PadC)") (class "Default")
      (node (ref "LED3") (pin "C") (pinfunction "C_C") (pintype "passive"))
      (node (ref "SJ3") (pin "3") (pinfunction "3_3") (pintype "passive"))
    )
    (net (code "42") (name "Net-(LED4-PadA)") (class "Default")
      (node (ref "LED4") (pin "A") (pinfunction "A_A") (pintype "passive"))
      (node (ref "R14") (pin "1") (pinfunction "1_1") (pintype "passive"))
    )
    (net (code "43") (name "Net-(Q1-2)") (class "Default")
      (node (ref "C11") (pin "1") (pinfunction "1_1") (pintype "passive"))
      (node (ref "Q1") (pin "3") (pinfunction "2_3") (pintype "passive"))
      (node (ref "U1") (pin "6") (pinfunction "PD1-OSC_OUT_6") (pintype "bidirectional"))
    )
    (net (code "44") (name "Net-(Q2-2)") (class "Default")
      (node (ref "C19") (pin "1") (pinfunction "1_1") (pintype "passive"))
      (node (ref "Q2") (pin "3") (pinfunction "2_3") (pintype "passive"))
      (node (ref "U2") (pin "10") (pinfunction "XC1_10") (pintype "input"))
    )
    (net (code "45") (name "Net-(R22-Pad1)") (class "Default")
      (node (ref "R22") (pin "1") (pinfunction "1_1") (pintype "passive"))
      (node (ref "U7") (pin "2") (pinfunction "2_2") (pintype "bidirectional"))
    )
    (net (code "46") (name "Net-(R23-Pad1)") (class "Default")
      (node (ref "R23") (pin "1") (pinfunction "1_1") (pintype "passive"))
      (node (ref "R24") (pin "2") (pinfunction "2_2") (pintype "passive"))
      (node (ref "U7") (pin "1") (pinfunction "1_1") (pintype "bidirectional"))
      (node (ref "U8") (pin "3") (pinfunction "3_3") (pintype "bidirectional"))
    )
    (net (code "47") (name "Net-(U1-PC14-OSC32_IN)") (class "Default")
      (node (ref "C8") (pin "1") (pinfunction "1_1") (pintype "passive"))
      (node (ref "U1") (pin "3") (pinfunction "PC14-OSC32_IN_3") (pintype "bidirectional"))
      (node (ref "U10") (pin "P$1") (pinfunction "XIN_P$1") (pintype "bidirectional"))
    )
    (net (code "48") (name "Net-(U1-PC15-OSC32_OUT)") (class "Default")
      (node (ref "C9") (pin "1") (pinfunction "1_1") (pintype "passive"))
      (node (ref "U1") (pin "4") (pinfunction "PC15-OSC32_OUT_4") (pintype "bidirectional"))
      (node (ref "U10") (pin "P$2") (pinfunction "XOUT_P$2") (pintype "bidirectional"))
    )
    (net (code "49") (name "Net-(U1-PD0-OSC_IN)") (class "Default")
      (node (ref "C10") (pin "1") (pinfunction "1_1") (pintype "passive"))
      (node (ref "Q1") (pin "1") (pinfunction "1_1") (pintype "passive"))
      (node (ref "U1") (pin "5") (pinfunction "PD0-OSC_IN_5") (pintype "bidirectional"))
    )
    (net (code "50") (name "Net-(U1-VDDA)") (class "Default")
      (node (ref "C5") (pin "1") (pinfunction "1_1") (pintype "passive"))
      (node (ref "C6") (pin "1") (pinfunction "1_1") (pintype "passive"))
      (node (ref "L1") (pin "1") (pinfunction "1_1") (pintype "passive"))
      (node (ref "U1") (pin "13") (pinfunction "VDDA_13") (pintype "bidirectional"))
    )
    (net (code "51") (name "Net-(U2-ANT1)") (class "Default")
      (node (ref "L3") (pin "2") (pinfunction "2_2") (pintype "passive"))
      (node (ref "L4") (pin "2") (pinfunction "2_2") (pintype "passive"))
      (node (ref "U2") (pin "12") (pinfunction "ANT1_12") (pintype "output"))
    )
    (net (code "52") (name "Net-(U2-ANT2)") (class "Default")
      (node (ref "L2") (pin "2") (pinfunction "2_2") (pintype "passive"))
      (node (ref "L3") (pin "1") (pinfunction "1_1") (pintype "passive"))
      (node (ref "U2") (pin "13") (pinfunction "ANT2_13") (pintype "output"))
    )
    (net (code "53") (name "Net-(U2-DVDD)") (class "Default")
      (node (ref "C20") (pin "1") (pinfunction "1_1") (pintype "passive"))
      (node (ref "U2") (pin "19") (pinfunction "DVDD_19") (pintype "power_in"))
    )
    (net (code "54") (name "Net-(U2-IREF)") (class "Default")
      (node (ref "R5") (pin "2") (pinfunction "2_2") (pintype "passive"))
      (node (ref "U2") (pin "16") (pinfunction "IREF_16") (pintype "input"))
    )
    (net (code "55") (name "Net-(U2-VDD_PA)") (class "Default")
      (node (ref "C16") (pin "1") (pinfunction "1_1") (pintype "passive"))
      (node (ref "C17") (pin "1") (pinfunction "1_1") (pintype "passive"))
      (node (ref "L4") (pin "1") (pinfunction "1_1") (pintype "passive"))
      (node (ref "U2") (pin "11") (pinfunction "VDD_PA_11") (pintype "power_in"))
    )
    (net (code "56") (name "Net-(U2-XC2)") (class "Default")
      (node (ref "C18") (pin "1") (pinfunction "1_1") (pintype "passive"))
      (node (ref "Q2") (pin "1") (pinfunction "1_1") (pintype "passive"))
      (node (ref "U2") (pin "9") (pinfunction "XC2_9") (pintype "input"))
    )
    (net (code "57") (name "Net-(U3-CHG)") (class "Default")
      (node (ref "RN2") (pin "1") (pinfunction "1_1") (pintype "passive"))
      (node (ref "RN2") (pin "2") (pinfunction "2_2") (pintype "passive"))
      (node (ref "U3") (pin "P$8") (pinfunction "CHG_P$8") (pintype "bidirectional"))
    )
    (net (code "58") (name "Net-(U3-IN)") (class "Default")
      (node (ref "C21") (pin "1") (pinfunction "1_1") (pintype "passive"))
      (node (ref "D1") (pin "C") (pinfunction "C_C") (pintype "passive"))
      (node (ref "D2") (pin "C") (pinfunction "C_C") (pintype "passive"))
      (node (ref "U3") (pin "P$1") (pinfunction "IN_P$1") (pintype "bidirectional"))
    )
    (net (code "59") (name "Net-(U3-ISET)") (class "Default")
      (node (ref "R8") (pin "2") (pinfunction "2_2") (pintype "passive"))
      (node (ref "U3") (pin "P$2") (pinfunction "ISET_P$2") (pintype "bidirectional"))
    )
    (net (code "60") (name "Net-(U3-ISET2)") (class "Default")
      (node (ref "R15") (pin "1") (pinfunction "1_1") (pintype "passive"))
      (node (ref "RN1") (pin "8") (pinfunction "8_8") (pintype "passive"))
      (node (ref "U3") (pin "P$10") (pinfunction "OUT_P$10") (pintype "bidirectional"))
      (node (ref "U3") (pin "P$7") (pinfunction "ISET2_P$7") (pintype "bidirectional"))
    )
    (net (code "61") (name "Net-(U3-PG)") (class "Default")
      (node (ref "RN2") (pin "3") (pinfunction "3_3") (pintype "passive"))
      (node (ref "RN2") (pin "4") (pinfunction "4_4") (pintype "passive"))
      (node (ref "U3") (pin "P$5") (pinfunction "PG_P$5") (pintype "bidirectional"))
    )
    (net (code "62") (name "Net-(U3-PRETERM)") (class "Default")
      (node (ref "R9") (pin "2") (pinfunction "2_2") (pintype "passive"))
      (node (ref "U3") (pin "P$4") (pinfunction "PRETERM_P$4") (pintype "bidirectional"))
    )
    (net (code "63") (name "Net-(U3-TS)") (class "Default")
      (node (ref "R10") (pin "1") (pinfunction "1_1") (pintype "passive"))
      (node (ref "U3") (pin "P$9") (pinfunction "TS_P$9") (pintype "bidirectional"))
    )
    (net (code "64") (name "Net-(U6-IO1_1)") (class "Default")
      (node (ref "U6") (pin "1") (pinfunction "IO1_1_1") (pintype "bidirectional"))
      (node (ref "X1") (pin "2") (pinfunction "2_2") (pintype "input"))
    )
    (net (code "65") (name "Net-(U6-IO2_1)") (class "Default")
      (node (ref "U6") (pin "3") (pinfunction "IO2_1_3") (pintype "bidirectional"))
      (node (ref "X1") (pin "3") (pinfunction "3_3") (pintype "input"))
    )
    (net (code "66") (name "Net-(U9-EN)") (class "Default")
      (node (ref "R11") (pin "1") (pinfunction "1_1") (pintype "passive"))
      (node (ref "U9") (pin "P5") (pinfunction "EN_P5") (pintype "bidirectional"))
    )
    (net (code "67") (name "Net-(U9-MODE)") (class "Default")
      (node (ref "R12") (pin "2") (pinfunction "2_2") (pintype "passive"))
      (node (ref "U9") (pin "P3") (pinfunction "MODE_P3") (pintype "bidirectional"))
    )
    (net (code "68") (name "Net-(U9-SW)") (class "Default")
      (node (ref "L5") (pin "2") (pinfunction "2_2") (pintype "passive"))
      (node (ref "U9") (pin "P2") (pinfunction "SW_P2") (pintype "bidirectional"))
    )
    (net (code "69") (name "PC13") (class "Default")
      (node (ref "SJ3") (pin "2") (pinfunction "2_2") (pintype "passive"))
      (node (ref "U1") (pin "2") (pinfunction "PC13-TAMPER-RTC_2") (pintype "bidirectional"))
    )
    (net (code "70") (name "RF24_CE") (class "Default")
      (node (ref "U1") (pin "59") (pinfunction "PB7/TIM4_CH2_59") (pintype "bidirectional"))
      (node (ref "U2") (pin "1") (pinfunction "CE_1") (pintype "input"))
    )
    (net (code "71") (name "RF24_CS") (class "Default")
      (node (ref "U1") (pin "58") (pinfunction "PB6/TIM4_CH1_58") (pintype "bidirectional"))
      (node (ref "U2") (pin "2") (pinfunction "CSN_2") (pintype "input"))
    )
    (net (code "72") (name "RF24_IRQ") (class "Default")
      (node (ref "U1") (pin "57") (pinfunction "PB5/TIM3_CH2_57") (pintype "bidirectional"))
      (node (ref "U2") (pin "6") (pinfunction "IRQ_6") (pintype "output"))
    )
    (net (code "73") (name "RST") (class "Default")
      (node (ref "C7") (pin "1") (pinfunction "1_1") (pintype "passive"))
      (node (ref "JP1") (pin "6") (pinfunction "6_6") (pintype "passive"))
      (node (ref "R1") (pin "1") (pinfunction "1_1") (pintype "passive"))
      (node (ref "S2") (pin "1") (pinfunction "1_1") (pintype "passive"))
      (node (ref "U$2") (pin "7") (pinfunction "NRST_7") (pintype "bidirectional"))
      (node (ref "U1") (pin "7") (pinfunction "NRST_7") (pintype "bidirectional"))
    )
    (net (code "74") (name "SPI_MISO") (class "Default")
      (node (ref "U1") (pin "51") (pinfunction "PC10/USART3_TX_51") (pintype "bidirectional"))
      (node (ref "U2") (pin "5") (pinfunction "MISO_5") (pintype "output"))
      (node (ref "U4") (pin "2") (pinfunction "SO_2") (pintype "bidirectional"))
      (node (ref "U5") (pin "2") (pinfunction "SO_2") (pintype "bidirectional"))
    )
    (net (code "75") (name "SPI_MOSI") (class "Default")
      (node (ref "U1") (pin "52") (pinfunction "PC11/USART3_RX_52") (pintype "bidirectional"))
      (node (ref "U2") (pin "4") (pinfunction "MOSI_4") (pintype "input"))
      (node (ref "U4") (pin "5") (pinfunction "SI_5") (pintype "bidirectional"))
      (node (ref "U5") (pin "5") (pinfunction "SI_5") (pintype "bidirectional"))
    )
    (net (code "76") (name "SPI_SCK") (class "Default")
      (node (ref "U1") (pin "53") (pinfunction "PC12_53") (pintype "bidirectional"))
      (node (ref "U2") (pin "3") (pinfunction "SCK_3") (pintype "input"))
      (node (ref "U4") (pin "6") (pinfunction "SCK_6") (pintype "bidirectional"))
      (node (ref "U5") (pin "6") (pinfunction "SCK_6") (pintype "bidirectional"))
    )
    (net (code "77") (name "SRAM_CS") (class "Default")
      (node (ref "U1") (pin "62") (pinfunction "PB9/TIM4_CH4_62") (pintype "bidirectional"))
      (node (ref "U5") (pin "1") (pinfunction "CS_1") (pintype "bidirectional"))
    )
    (net (code "78") (name "SRAM_HOLD") (class "Default")
      (node (ref "R4") (pin "1") (pinfunction "1_1") (pintype "passive"))
      (node (ref "U5") (pin "7") (pinfunction "HOLD_7") (pintype "bidirectional"))
    )
    (net (code "79") (name "T0") (class "Default")
      (node (ref "JP2") (pin "1") (pinfunction "1_1") (pintype "passive"))
      (node (ref "U1") (pin "38") (pinfunction "PC7/TIM3_CH2_38") (pintype "bidirectional"))
    )
    (net (code "80") (name "T1") (class "Default")
      (node (ref "JP2") (pin "2") (pinfunction "2_2") (pintype "passive"))
      (node (ref "U1") (pin "37") (pinfunction "PC6/TIM3_CH1_37") (pintype "bidirectional"))
    )
    (net (code "81") (name "TA0") (class "Default")
      (node (ref "JP2") (pin "3") (pinfunction "3_3") (pintype "passive"))
      (node (ref "U1") (pin "36") (pinfunction "PB15/ADC_IN21/TIM11_CH1_36") (pintype "bidirectional"))
    )
    (net (code "82") (name "TA1") (class "Default")
      (node (ref "JP2") (pin "4") (pinfunction "4_4") (pintype "passive"))
      (node (ref "U1") (pin "35") (pinfunction "PB14/ADC_IN20/TIM9_CH2_35") (pintype "bidirectional"))
    )
    (net (code "83") (name "TA2") (class "Default")
      (node (ref "JP2") (pin "5") (pinfunction "5_5") (pintype "passive"))
      (node (ref "U1") (pin "34") (pinfunction "PB13/ADC_IN19/TIM9_CH1_34") (pintype "bidirectional"))
    )
    (net (code "84") (name "TA3") (class "Default")
      (node (ref "JP2") (pin "6") (pinfunction "6_6") (pintype "passive"))
      (node (ref "U1") (pin "33") (pinfunction "PB12/ADC_IN18/TIM10_CH1_33") (pintype "bidirectional"))
    )
    (net (code "85") (name "TA4") (class "Default")
      (node (ref "JP2") (pin "7") (pinfunction "7_7") (pintype "passive"))
      (node (ref "U1") (pin "27") (pinfunction "PB1/ADC_IN9/TIM3_CH4_27") (pintype "bidirectional"))
    )
    (net (code "86") (name "TA5") (class "Default")
      (node (ref "JP2") (pin "8") (pinfunction "8_8") (pintype "passive"))
      (node (ref "U1") (pin "26") (pinfunction "PB0/ADC_IN8/TIM3_CH3_26") (pintype "bidirectional"))
    )
    (net (code "87") (name "TA6") (class "Default")
      (node (ref "JP2") (pin "9") (pinfunction "9_9") (pintype "passive"))
      (node (ref "U1") (pin "15") (pinfunction "PA1/ADC_IN1/TIM2_CH2_15") (pintype "bidirectional"))
    )
    (net (code "88") (name "USB_DISC") (class "Default")
      (node (ref "R25") (pin "2") (pinfunction "2_2") (pintype "passive"))
      (node (ref "U1") (pin "54") (pinfunction "PD2_54") (pintype "bidirectional"))
      (node (ref "U8") (pin "1") (pinfunction "1_1") (pintype "bidirectional"))
    )
    (net (code "89") (name "USB_DM") (class "Default")
      (node (ref "U1") (pin "44") (pinfunction "PA11/USB_DM_44") (pintype "bidirectional"))
      (node (ref "U6") (pin "6") (pinfunction "IO1_2_6") (pintype "bidirectional"))
    )
    (net (code "90") (name "USB_DP") (class "Default")
      (node (ref "R22") (pin "2") (pinfunction "2_2") (pintype "passive"))
      (node (ref "U1") (pin "45") (pinfunction "PA12/USB_DP_45") (pintype "bidirectional"))
      (node (ref "U6") (pin "4") (pinfunction "IO2_2_4") (pintype "bidirectional"))
    )
    (net (code "91") (name "V+") (class "Default")
      (node (ref "D1") (pin "A") (pinfunction "A_A") (pintype "passive"))
      (node (ref "JP5") (pin "2") (pinfunction "2_2") (pintype "passive"))
      (node (ref "SJ4") (pin "3") (pinfunction "3_3") (pintype "passive"))
    )
    (net (code "92") (name "VCC") (class "Default")
      (node (ref "C23") (pin "1") (pinfunction "1_1") (pintype "passive"))
      (node (ref "JP6") (pin "2") (pinfunction "2_2") (pintype "passive"))
      (node (ref "LED1") (pin "C") (pinfunction "C_C") (pintype "passive"))
      (node (ref "LED2") (pin "C") (pinfunction "C_C") (pintype "passive"))
      (node (ref "R11") (pin "2") (pinfunction "2_2") (pintype "passive"))
      (node (ref "R15") (pin "2") (pinfunction "2_2") (pintype "passive"))
      (node (ref "RN1") (pin "5") (pinfunction "5_5") (pintype "passive"))
      (node (ref "U9") (pin "P4") (pinfunction "VIN_P4") (pintype "bidirectional"))
    )
    (net (code "93") (name "unconnected-(JP7-Pad3)") (class "Default")
      (node (ref "JP7") (pin "3") (pinfunction "3_3") (pintype "passive"))
    )
    (net (code "94") (name "unconnected-(U$2-NC-Pad10)") (class "Default")
      (node (ref "U$2") (pin "10") (pinfunction "NC_10") (pintype "bidirectional"))
    )
    (net (code "95") (name "unconnected-(U3-NC-PadP$6)") (class "Default")
      (node (ref "U3") (pin "P$6") (pinfunction "NC_P$6") (pintype "bidirectional"))
    )
    (net (code "96") (name "unconnected-(U5-NC-Pad3)") (class "Default")
      (node (ref "U5") (pin "3") (pinfunction "NC_3") (pintype "bidirectional"))
    )
  )
)
